# LCD.net
KiCad netlist of a schematic drawn in Altium Designer
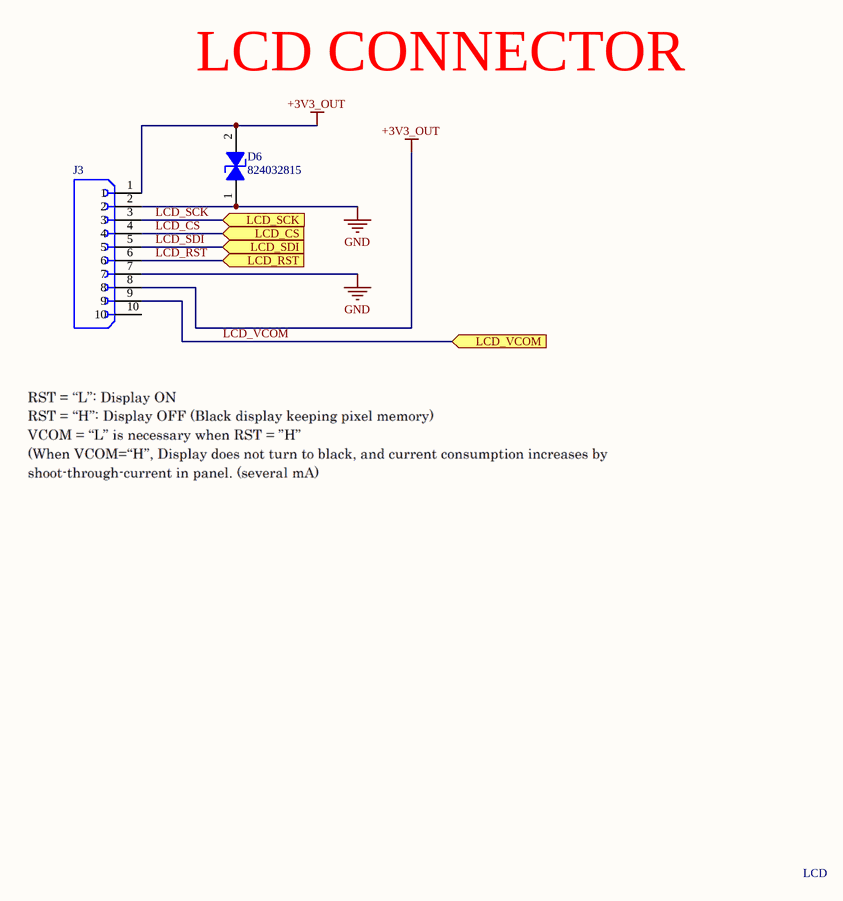
[diagram p0: LCD.SchDoc]

(export (version "E")
  (design (tool "Eeschema 10.0.6"))
  (components
    (comp (ref "D6")
      (value "824032815")
      (footprint "WE-TVS_DFN1610-2L")
      (description "824032815 Tvs Diode, Bidir, 5V, Dfn1610 Rohs Compliant: Yes ¦Wurth Elektronik 824032815")
      (libsource (lib "LPEDT_Components") (part "TVS Diode ESD Protection"))
    )
    (comp (ref "J3")
      (value "~")
      (footprint "HRS_TF13BA-10S-0.4SH(800)")
      (fields (field (name "MP") "TF13BA-10S-0.4SH(800)"))
      (libsource (lib "LPEDT_Components") (part "TF13BA-10S-0.4SH(800)"))
    )
  )
  (nets
    (net (code "1") (name "+3V3_OUT") (class "Default")
      (node (ref "D6") (pin "2") (pinfunction "GND_2") (pintype "passive"))
      (node (ref "J3") (pin "1") (pinfunction "1_1") (pintype "passive"))
      (node (ref "J3") (pin "8") (pinfunction "8_8") (pintype "passive"))
    )
    (net (code "2") (name "/LCD_CS") (class "Default")
      (node (ref "J3") (pin "4") (pinfunction "4_4") (pintype "passive"))
    )
    (net (code "3") (name "/LCD_RST") (class "Default")
      (node (ref "J3") (pin "6") (pinfunction "6_6") (pintype "passive"))
    )
    (net (code "4") (name "/LCD_SCK") (class "Default")
      (node (ref "J3") (pin "3") (pinfunction "3_3") (pintype "passive"))
    )
    (net (code "5") (name "/LCD_SDI") (class "Default")
      (node (ref "J3") (pin "5") (pinfunction "5_5") (pintype "passive"))
    )
    (net (code "6") (name "/LCD_VCOM") (class "Default")
      (node (ref "J3") (pin "9") (pinfunction "9_9") (pintype "passive"))
    )
    (net (code "7") (name "GND") (class "Default")
      (node (ref "D6") (pin "1") (pinfunction "I/O_1_1") (pintype "passive"))
      (node (ref "J3") (pin "2") (pinfunction "2_2") (pintype "passive"))
      (node (ref "J3") (pin "7") (pinfunction "7_7") (pintype "passive"))
    )
    (net (code "8") (name "unconnected-(J3-Pad10)") (class "Default")
      (node (ref "J3") (pin "10") (pinfunction "10_10") (pintype "passive"))
    )
  )
)
